# DA_uno_shield_3_0.net
KiCad netlist of a schematic drawn in EAGLE
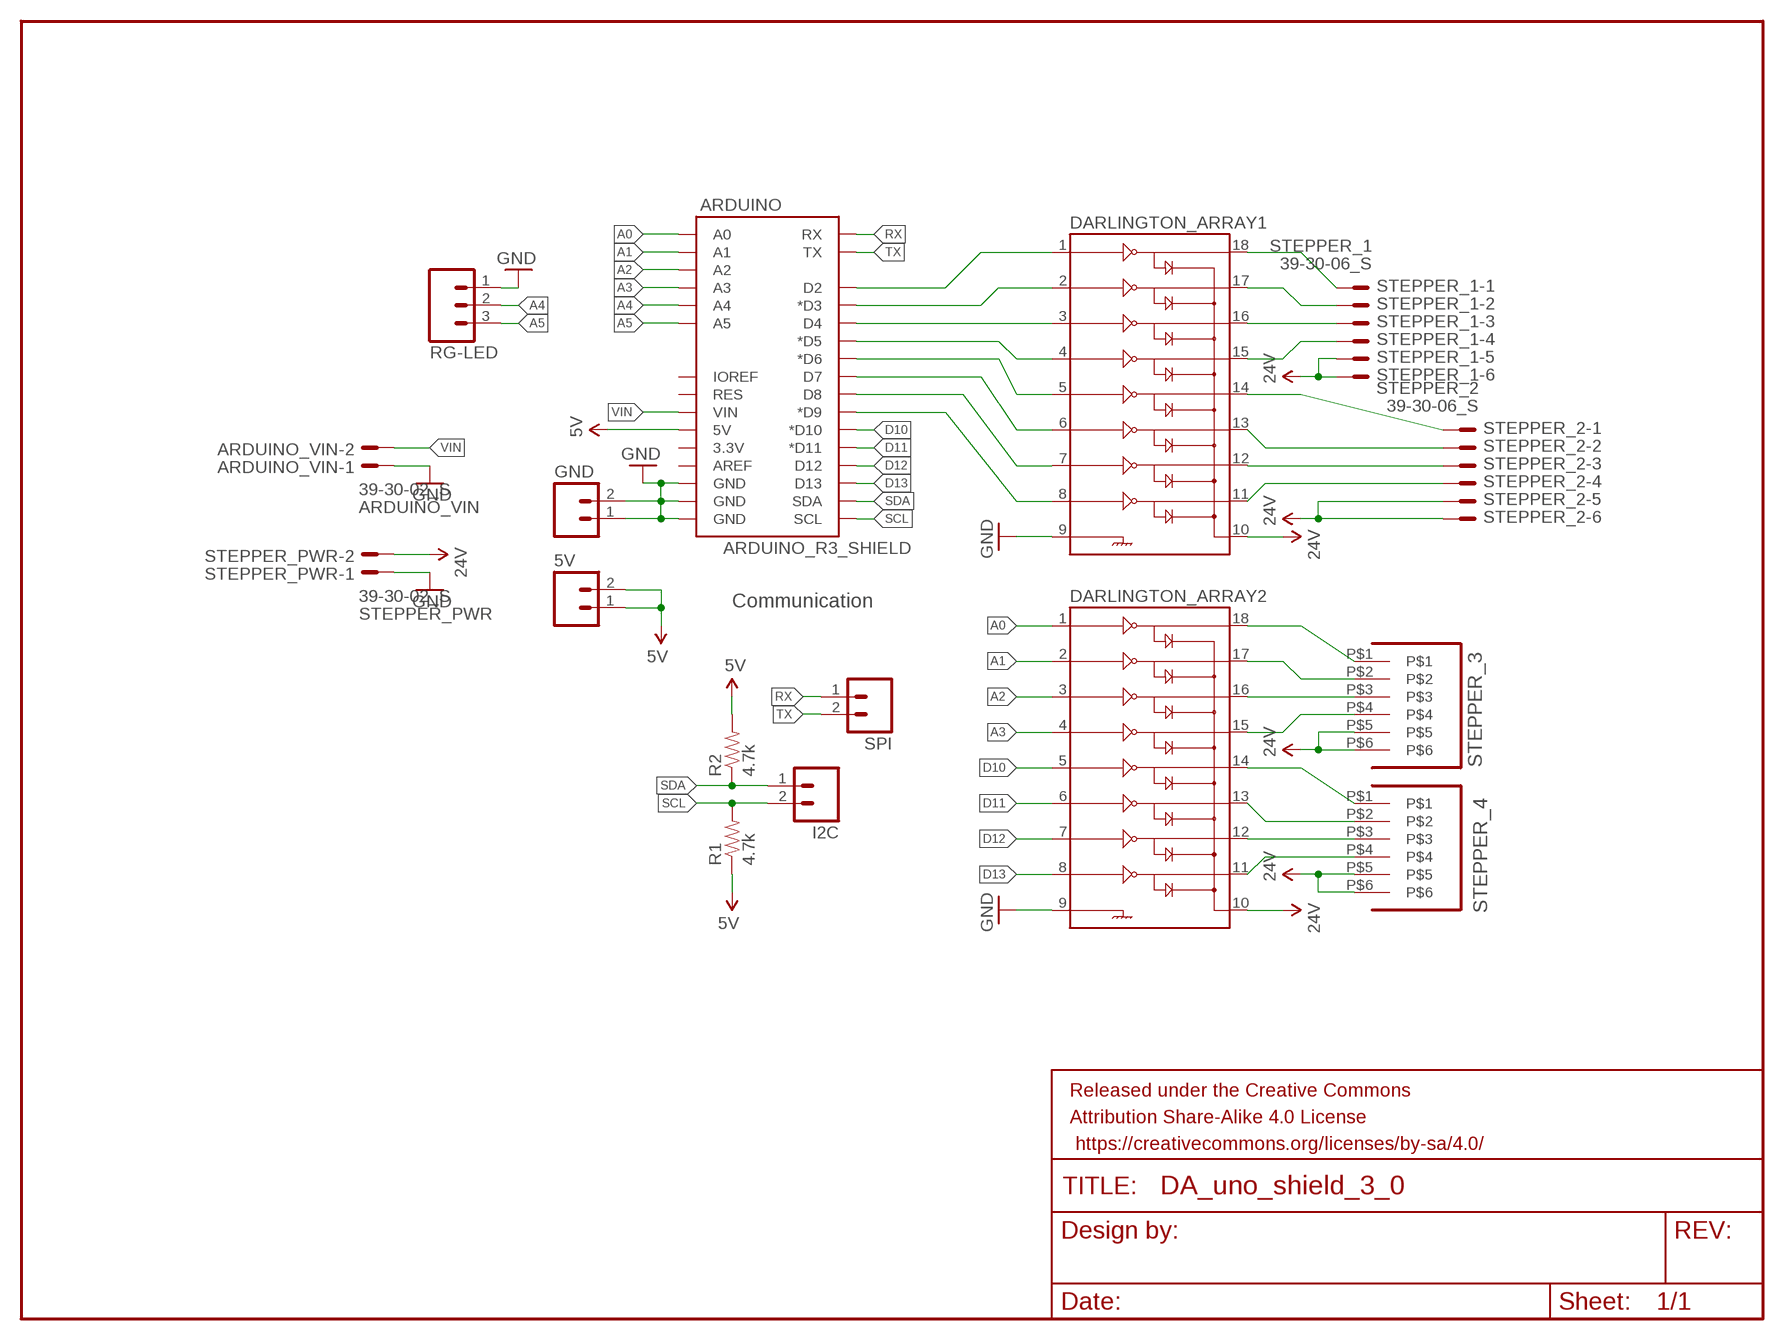
[diagram p0: schematic, sheet 1]

(export (version "E")
  (design (tool "Eeschema 10.0.6"))
  (components
    (comp (ref "5V")
      (value "M021X02_NO_SILK")
      (footprint "eagle-import:1X02_NO_SILK")
      (libsource (lib "eagle-import") (part "M021X02_NO_SILK"))
    )
    (comp (ref "ARDUINO")
      (value "ARDUINO_R3_SHIELD")
      (footprint "eagle-import:UNO_R3_SHIELD")
      (libsource (lib "eagle-import") (part "ARDUINO_R3_SHIELD"))
    )
    (comp (ref "ARDUINO_VIN")
      (value "39-30-02_S")
      (footprint "eagle-import:39-30-_02_")
      (libsource (lib "eagle-import") (part "39-30-?02?_S"))
    )
    (comp (ref "DARLINGTON_ARRAY1")
      (value "ULN2803DIP")
      (footprint "eagle-import:DIL18")
      (libsource (lib "eagle-import") (part "ULN2803DIP"))
    )
    (comp (ref "DARLINGTON_ARRAY2")
      (value "ULN2803DIP")
      (footprint "eagle-import:DIL18")
      (libsource (lib "eagle-import") (part "ULN2803DIP"))
    )
    (comp (ref "FRAME1")
      (value "FRAME-LETTER")
      (footprint "eagle-import:CREATIVE_COMMONS")
      (libsource (lib "eagle-import") (part "FRAME-LETTER"))
    )
    (comp (ref "GND")
      (value "M021X02_NO_SILK")
      (footprint "eagle-import:1X02_NO_SILK")
      (libsource (lib "eagle-import") (part "M021X02_NO_SILK"))
    )
    (comp (ref "I2C")
      (value "M021X02_NO_SILK")
      (footprint "eagle-import:1X02_NO_SILK")
      (libsource (lib "eagle-import") (part "M021X02_NO_SILK"))
    )
    (comp (ref "R1")
      (value "4.7k")
      (footprint "eagle-import:AXIAL-0.3-KIT")
      (libsource (lib "eagle-import") (part "RESISTORKIT"))
    )
    (comp (ref "R2")
      (value "4.7k")
      (footprint "eagle-import:AXIAL-0.3-KIT")
      (libsource (lib "eagle-import") (part "RESISTORKIT"))
    )
    (comp (ref "RG-LED")
      (value "M03LOCK_NO_SILK")
      (footprint "eagle-import:1X03_LOCK_NO_SILK")
      (libsource (lib "eagle-import") (part "M03LOCK_NO_SILK"))
    )
    (comp (ref "SPI")
      (value "M021X02_NO_SILK")
      (footprint "eagle-import:1X02_NO_SILK")
      (libsource (lib "eagle-import") (part "M021X02_NO_SILK"))
    )
    (comp (ref "STEPPER_1")
      (value "39-30-06_S")
      (footprint "eagle-import:39-30-_06_")
      (libsource (lib "eagle-import") (part "39-30-?06?_S"))
    )
    (comp (ref "STEPPER_2")
      (value "39-30-06_S")
      (footprint "eagle-import:39-30-_06_")
      (libsource (lib "eagle-import") (part "39-30-?06?_S"))
    )
    (comp (ref "STEPPER_3")
      (value "39-29-06")
      (footprint "eagle-import:39-29-_06_")
      (libsource (lib "eagle-import") (part "39-29-?06?"))
    )
    (comp (ref "STEPPER_4")
      (value "39-29-06")
      (footprint "eagle-import:39-29-_06_")
      (libsource (lib "eagle-import") (part "39-29-?06?"))
    )
    (comp (ref "STEPPER_PWR")
      (value "39-30-02_S")
      (footprint "eagle-import:39-30-_02_")
      (libsource (lib "eagle-import") (part "39-30-?02?_S"))
    )
  )
  (nets
    (net (code "1") (name "5V") (class "Default")
      (node (ref "5V") (pin "1") (pinfunction "1_1") (pintype "passive"))
      (node (ref "5V") (pin "2") (pinfunction "2_2") (pintype "passive"))
      (node (ref "ARDUINO") (pin "5V") (pinfunction "5V_5V") (pintype "bidirectional"))
      (node (ref "R1") (pin "P$1") (pinfunction "1_P$1") (pintype "passive"))
      (node (ref "R2") (pin "P$2") (pinfunction "2_P$2") (pintype "passive"))
    )
    (net (code "2") (name "24V") (class "Default")
      (node (ref "DARLINGTON_ARRAY1") (pin "10") (pinfunction "10_10") (pintype "bidirectional"))
      (node (ref "DARLINGTON_ARRAY2") (pin "10") (pinfunction "10_10") (pintype "bidirectional"))
      (node (ref "STEPPER_1") (pin "5") (pinfunction "P_5") (pintype "passive"))
      (node (ref "STEPPER_1") (pin "6") (pinfunction "P_6") (pintype "passive"))
      (node (ref "STEPPER_2") (pin "5") (pinfunction "P_5") (pintype "passive"))
      (node (ref "STEPPER_2") (pin "6") (pinfunction "P_6") (pintype "passive"))
      (node (ref "STEPPER_3") (pin "P$5") (pinfunction "P$5_P$5") (pintype "bidirectional"))
      (node (ref "STEPPER_3") (pin "P$6") (pinfunction "P$6_P$6") (pintype "bidirectional"))
      (node (ref "STEPPER_4") (pin "P$5") (pinfunction "P$5_P$5") (pintype "bidirectional"))
      (node (ref "STEPPER_4") (pin "P$6") (pinfunction "P$6_P$6") (pintype "bidirectional"))
      (node (ref "STEPPER_PWR") (pin "2") (pinfunction "P_2") (pintype "passive"))
    )
    (net (code "3") (name "A0") (class "Default")
      (node (ref "ARDUINO") (pin "A0") (pinfunction "A0_A0") (pintype "bidirectional"))
      (node (ref "DARLINGTON_ARRAY2") (pin "1") (pinfunction "1_1") (pintype "bidirectional"))
    )
    (net (code "4") (name "A1") (class "Default")
      (node (ref "ARDUINO") (pin "A1") (pinfunction "A1_A1") (pintype "bidirectional"))
      (node (ref "DARLINGTON_ARRAY2") (pin "2") (pinfunction "2_2") (pintype "bidirectional"))
    )
    (net (code "5") (name "A2") (class "Default")
      (node (ref "ARDUINO") (pin "A2") (pinfunction "A2_A2") (pintype "bidirectional"))
      (node (ref "DARLINGTON_ARRAY2") (pin "3") (pinfunction "3_3") (pintype "bidirectional"))
    )
    (net (code "6") (name "A3") (class "Default")
      (node (ref "ARDUINO") (pin "A3") (pinfunction "A3_A3") (pintype "bidirectional"))
      (node (ref "DARLINGTON_ARRAY2") (pin "4") (pinfunction "4_4") (pintype "bidirectional"))
    )
    (net (code "7") (name "A4") (class "Default")
      (node (ref "ARDUINO") (pin "A4") (pinfunction "A4_A4") (pintype "bidirectional"))
      (node (ref "RG-LED") (pin "2") (pinfunction "2_2") (pintype "passive"))
    )
    (net (code "8") (name "A5") (class "Default")
      (node (ref "ARDUINO") (pin "A5") (pinfunction "A5_A5") (pintype "bidirectional"))
      (node (ref "RG-LED") (pin "3") (pinfunction "3_3") (pintype "passive"))
    )
    (net (code "9") (name "D10") (class "Default")
      (node (ref "ARDUINO") (pin "D10") (pinfunction "*D10_D10") (pintype "bidirectional"))
      (node (ref "DARLINGTON_ARRAY2") (pin "5") (pinfunction "5_5") (pintype "bidirectional"))
    )
    (net (code "10") (name "D11") (class "Default")
      (node (ref "ARDUINO") (pin "D11") (pinfunction "*D11_D11") (pintype "bidirectional"))
      (node (ref "DARLINGTON_ARRAY2") (pin "6") (pinfunction "6_6") (pintype "bidirectional"))
    )
    (net (code "11") (name "D12") (class "Default")
      (node (ref "ARDUINO") (pin "D12") (pinfunction "D12_D12") (pintype "bidirectional"))
      (node (ref "DARLINGTON_ARRAY2") (pin "7") (pinfunction "7_7") (pintype "bidirectional"))
    )
    (net (code "12") (name "D13") (class "Default")
      (node (ref "ARDUINO") (pin "D13") (pinfunction "D13_D13") (pintype "bidirectional"))
      (node (ref "DARLINGTON_ARRAY2") (pin "8") (pinfunction "8_8") (pintype "bidirectional"))
    )
    (net (code "13") (name "GND") (class "Default")
      (node (ref "ARDUINO") (pin "GND@0") (pinfunction "GND_GND@0") (pintype "bidirectional"))
      (node (ref "ARDUINO") (pin "GND@1") (pinfunction "GND_GND@1") (pintype "bidirectional"))
      (node (ref "ARDUINO") (pin "GND@2") (pinfunction "GND_GND@2") (pintype "bidirectional"))
      (node (ref "ARDUINO_VIN") (pin "1") (pinfunction "P_1") (pintype "passive"))
      (node (ref "DARLINGTON_ARRAY1") (pin "9") (pinfunction "9_9") (pintype "bidirectional"))
      (node (ref "DARLINGTON_ARRAY2") (pin "9") (pinfunction "9_9") (pintype "bidirectional"))
      (node (ref "GND") (pin "1") (pinfunction "1_1") (pintype "passive"))
      (node (ref "GND") (pin "2") (pinfunction "2_2") (pintype "passive"))
      (node (ref "RG-LED") (pin "1") (pinfunction "1_1") (pintype "passive"))
      (node (ref "STEPPER_PWR") (pin "1") (pinfunction "P_1") (pintype "passive"))
    )
    (net (code "14") (name "Net-(ARDUINO-*D3)") (class "Default")
      (node (ref "ARDUINO") (pin "D3") (pinfunction "*D3_D3") (pintype "bidirectional"))
      (node (ref "DARLINGTON_ARRAY1") (pin "2") (pinfunction "2_2") (pintype "bidirectional"))
    )
    (net (code "15") (name "Net-(ARDUINO-*D5)") (class "Default")
      (node (ref "ARDUINO") (pin "D5") (pinfunction "*D5_D5") (pintype "bidirectional"))
      (node (ref "DARLINGTON_ARRAY1") (pin "4") (pinfunction "4_4") (pintype "bidirectional"))
    )
    (net (code "16") (name "Net-(ARDUINO-*D6)") (class "Default")
      (node (ref "ARDUINO") (pin "D6") (pinfunction "*D6_D6") (pintype "bidirectional"))
      (node (ref "DARLINGTON_ARRAY1") (pin "5") (pinfunction "5_5") (pintype "bidirectional"))
    )
    (net (code "17") (name "Net-(ARDUINO-*D9)") (class "Default")
      (node (ref "ARDUINO") (pin "D9") (pinfunction "*D9_D9") (pintype "bidirectional"))
      (node (ref "DARLINGTON_ARRAY1") (pin "8") (pinfunction "8_8") (pintype "bidirectional"))
    )
    (net (code "18") (name "Net-(ARDUINO-PadD2)") (class "Default")
      (node (ref "ARDUINO") (pin "D2") (pinfunction "D2_D2") (pintype "bidirectional"))
      (node (ref "DARLINGTON_ARRAY1") (pin "1") (pinfunction "1_1") (pintype "bidirectional"))
    )
    (net (code "19") (name "Net-(ARDUINO-PadD4)") (class "Default")
      (node (ref "ARDUINO") (pin "D4") (pinfunction "D4_D4") (pintype "bidirectional"))
      (node (ref "DARLINGTON_ARRAY1") (pin "3") (pinfunction "3_3") (pintype "bidirectional"))
    )
    (net (code "20") (name "Net-(ARDUINO-PadD7)") (class "Default")
      (node (ref "ARDUINO") (pin "D7") (pinfunction "D7_D7") (pintype "bidirectional"))
      (node (ref "DARLINGTON_ARRAY1") (pin "6") (pinfunction "6_6") (pintype "bidirectional"))
    )
    (net (code "21") (name "Net-(ARDUINO-PadD8)") (class "Default")
      (node (ref "ARDUINO") (pin "D8") (pinfunction "D8_D8") (pintype "bidirectional"))
      (node (ref "DARLINGTON_ARRAY1") (pin "7") (pinfunction "7_7") (pintype "bidirectional"))
    )
    (net (code "22") (name "Net-(DARLINGTON_ARRAY2-Pad11)") (class "Default")
      (node (ref "DARLINGTON_ARRAY2") (pin "11") (pinfunction "11_11") (pintype "bidirectional"))
      (node (ref "STEPPER_4") (pin "P$4") (pinfunction "P$4_P$4") (pintype "bidirectional"))
    )
    (net (code "23") (name "Net-(DARLINGTON_ARRAY2-Pad12)") (class "Default")
      (node (ref "DARLINGTON_ARRAY2") (pin "12") (pinfunction "12_12") (pintype "bidirectional"))
      (node (ref "STEPPER_4") (pin "P$3") (pinfunction "P$3_P$3") (pintype "bidirectional"))
    )
    (net (code "24") (name "Net-(DARLINGTON_ARRAY2-Pad13)") (class "Default")
      (node (ref "DARLINGTON_ARRAY2") (pin "13") (pinfunction "13_13") (pintype "bidirectional"))
      (node (ref "STEPPER_4") (pin "P$2") (pinfunction "P$2_P$2") (pintype "bidirectional"))
    )
    (net (code "25") (name "Net-(DARLINGTON_ARRAY2-Pad14)") (class "Default")
      (node (ref "DARLINGTON_ARRAY2") (pin "14") (pinfunction "14_14") (pintype "bidirectional"))
      (node (ref "STEPPER_4") (pin "P$1") (pinfunction "P$1_P$1") (pintype "bidirectional"))
    )
    (net (code "26") (name "Net-(DARLINGTON_ARRAY2-Pad15)") (class "Default")
      (node (ref "DARLINGTON_ARRAY2") (pin "15") (pinfunction "15_15") (pintype "bidirectional"))
      (node (ref "STEPPER_3") (pin "P$4") (pinfunction "P$4_P$4") (pintype "bidirectional"))
    )
    (net (code "27") (name "Net-(DARLINGTON_ARRAY2-Pad16)") (class "Default")
      (node (ref "DARLINGTON_ARRAY2") (pin "16") (pinfunction "16_16") (pintype "bidirectional"))
      (node (ref "STEPPER_3") (pin "P$3") (pinfunction "P$3_P$3") (pintype "bidirectional"))
    )
    (net (code "28") (name "Net-(DARLINGTON_ARRAY2-Pad17)") (class "Default")
      (node (ref "DARLINGTON_ARRAY2") (pin "17") (pinfunction "17_17") (pintype "bidirectional"))
      (node (ref "STEPPER_3") (pin "P$2") (pinfunction "P$2_P$2") (pintype "bidirectional"))
    )
    (net (code "29") (name "Net-(DARLINGTON_ARRAY2-Pad18)") (class "Default")
      (node (ref "DARLINGTON_ARRAY2") (pin "18") (pinfunction "18_18") (pintype "bidirectional"))
      (node (ref "STEPPER_3") (pin "P$1") (pinfunction "P$1_P$1") (pintype "bidirectional"))
    )
    (net (code "30") (name "Net-(STEPPER_1A-P)") (class "Default")
      (node (ref "DARLINGTON_ARRAY1") (pin "18") (pinfunction "18_18") (pintype "bidirectional"))
      (node (ref "STEPPER_1") (pin "1") (pinfunction "P_1") (pintype "passive"))
    )
    (net (code "31") (name "Net-(STEPPER_1B-P)") (class "Default")
      (node (ref "DARLINGTON_ARRAY1") (pin "17") (pinfunction "17_17") (pintype "bidirectional"))
      (node (ref "STEPPER_1") (pin "2") (pinfunction "P_2") (pintype "passive"))
    )
    (net (code "32") (name "Net-(STEPPER_1C-P)") (class "Default")
      (node (ref "DARLINGTON_ARRAY1") (pin "16") (pinfunction "16_16") (pintype "bidirectional"))
      (node (ref "STEPPER_1") (pin "3") (pinfunction "P_3") (pintype "passive"))
    )
    (net (code "33") (name "Net-(STEPPER_1D-P)") (class "Default")
      (node (ref "DARLINGTON_ARRAY1") (pin "15") (pinfunction "15_15") (pintype "bidirectional"))
      (node (ref "STEPPER_1") (pin "4") (pinfunction "P_4") (pintype "passive"))
    )
    (net (code "34") (name "Net-(STEPPER_2A-P)") (class "Default")
      (node (ref "DARLINGTON_ARRAY1") (pin "14") (pinfunction "14_14") (pintype "bidirectional"))
      (node (ref "STEPPER_2") (pin "1") (pinfunction "P_1") (pintype "passive"))
    )
    (net (code "35") (name "Net-(STEPPER_2B-P)") (class "Default")
      (node (ref "DARLINGTON_ARRAY1") (pin "13") (pinfunction "13_13") (pintype "bidirectional"))
      (node (ref "STEPPER_2") (pin "2") (pinfunction "P_2") (pintype "passive"))
    )
    (net (code "36") (name "Net-(STEPPER_2C-P)") (class "Default")
      (node (ref "DARLINGTON_ARRAY1") (pin "12") (pinfunction "12_12") (pintype "bidirectional"))
      (node (ref "STEPPER_2") (pin "3") (pinfunction "P_3") (pintype "passive"))
    )
    (net (code "37") (name "Net-(STEPPER_2D-P)") (class "Default")
      (node (ref "DARLINGTON_ARRAY1") (pin "11") (pinfunction "11_11") (pintype "bidirectional"))
      (node (ref "STEPPER_2") (pin "4") (pinfunction "P_4") (pintype "passive"))
    )
    (net (code "38") (name "RX") (class "Default")
      (node (ref "ARDUINO") (pin "RX") (pinfunction "RX_RX") (pintype "bidirectional"))
      (node (ref "SPI") (pin "1") (pinfunction "1_1") (pintype "passive"))
    )
    (net (code "39") (name "SCL") (class "Default")
      (node (ref "ARDUINO") (pin "SCL") (pinfunction "SCL_SCL") (pintype "bidirectional"))
      (node (ref "I2C") (pin "2") (pinfunction "2_2") (pintype "passive"))
      (node (ref "R1") (pin "P$2") (pinfunction "2_P$2") (pintype "passive"))
    )
    (net (code "40") (name "SDA") (class "Default")
      (node (ref "ARDUINO") (pin "SDA") (pinfunction "SDA_SDA") (pintype "bidirectional"))
      (node (ref "I2C") (pin "1") (pinfunction "1_1") (pintype "passive"))
      (node (ref "R2") (pin "P$1") (pinfunction "1_P$1") (pintype "passive"))
    )
    (net (code "41") (name "TX") (class "Default")
      (node (ref "ARDUINO") (pin "TX") (pinfunction "TX_TX") (pintype "bidirectional"))
      (node (ref "SPI") (pin "2") (pinfunction "2_2") (pintype "passive"))
    )
    (net (code "42") (name "VIN") (class "Default")
      (node (ref "ARDUINO") (pin "VIN") (pinfunction "VIN_VIN") (pintype "bidirectional"))
      (node (ref "ARDUINO_VIN") (pin "2") (pinfunction "P_2") (pintype "passive"))
    )
    (net (code "43") (name "unconnected-(ARDUINO-Pad3.3V)") (class "Default")
      (node (ref "ARDUINO") (pin "3.3V") (pinfunction "3.3V_3.3V") (pintype "bidirectional"))
    )
    (net (code "44") (name "unconnected-(ARDUINO-PadAREF)") (class "Default")
      (node (ref "ARDUINO") (pin "AREF") (pinfunction "AREF_AREF") (pintype "bidirectional"))
    )
    (net (code "45") (name "unconnected-(ARDUINO-PadIOREF)") (class "Default")
      (node (ref "ARDUINO") (pin "IOREF") (pinfunction "IOREF_IOREF") (pintype "bidirectional"))
    )
    (net (code "46") (name "unconnected-(ARDUINO-PadRES)") (class "Default")
      (node (ref "ARDUINO") (pin "RES") (pinfunction "RES_RES") (pintype "bidirectional"))
    )
  )
)
